# Erls_MCP73871_Solar_Charger_v1.net
KiCad netlist of a schematic drawn in EAGLE
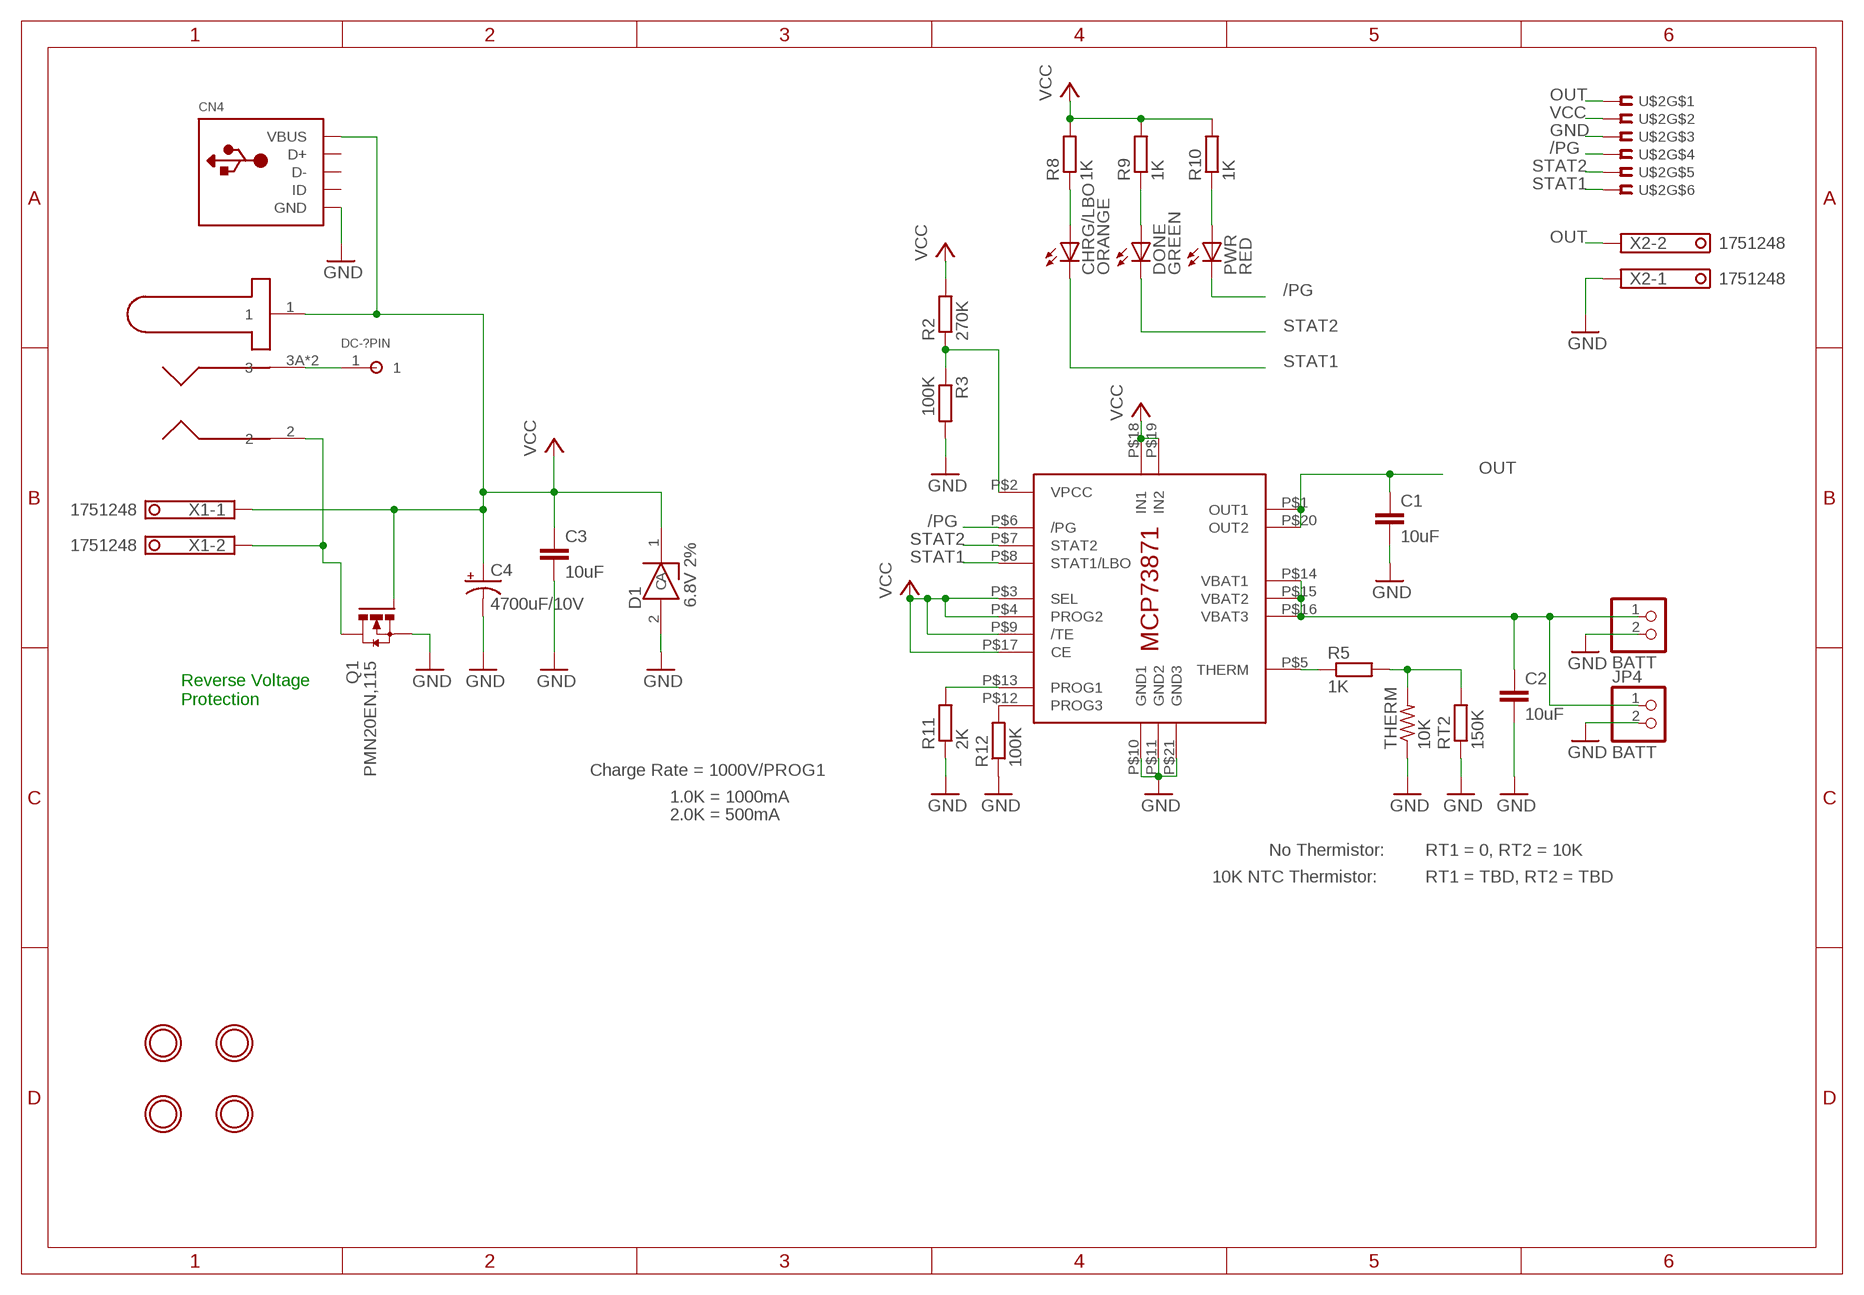
[diagram p0: schematic, sheet 1]

(export (version "E")
  (design (tool "Eeschema 10.0.6"))
  (components
    (comp (ref "BATT")
      (value "JST_2PIN-SMT-RA")
      (footprint "eagle-import:JST-PH-2-SMT-RA")
      (libsource (lib "eagle-import") (part "JST_2PIN-SMT-RA"))
    )
    (comp (ref "C1")
      (value "10uF")
      (footprint "eagle-import:C0603K")
      (libsource (lib "eagle-import") (part "C-EUC0603K"))
    )
    (comp (ref "C2")
      (value "10uF")
      (footprint "eagle-import:C0603K")
      (libsource (lib "eagle-import") (part "C-EUC0603K"))
    )
    (comp (ref "C3")
      (value "10uF")
      (footprint "eagle-import:C0603K")
      (libsource (lib "eagle-import") (part "C-EUC0603K"))
    )
    (comp (ref "C4")
      (value "4700uF/10V")
      (footprint "eagle-import:E5-13")
      (libsource (lib "eagle-import") (part "CPOL-USE5-13"))
    )
    (comp (ref "CHRG/LBO")
      (value "ORANGE")
      (footprint "eagle-import:CHIPLED_0603")
      (libsource (lib "eagle-import") (part "LED-0603"))
    )
    (comp (ref "CN4")
      (value "USB-MINIB-ONSHORE-M26FTR")
      (footprint "eagle-import:USB-MINIB-ONSHORE-M26FTR")
      (libsource (lib "eagle-import") (part "USB-MINIB-ONSHORE-M26FTR"))
    )
    (comp (ref "D1")
      (value "6.8V 2%")
      (footprint "eagle-import:SOD323")
      (libsource (lib "eagle-import") (part "ZENER-MM3Z6V8ST1G"))
    )
    (comp (ref "DC-?PIN")
      (value "PAD-1-TH")
      (footprint "eagle-import:PAD-1-TH")
      (libsource (lib "eagle-import") (part "PAD-1-TH"))
    )
    (comp (ref "DONE")
      (value "GREEN")
      (footprint "eagle-import:CHIPLED_0603")
      (libsource (lib "eagle-import") (part "LED-0603"))
    )
    (comp (ref "JP4")
      (value "BATT")
      (footprint "eagle-import:1X02_ROUND")
      (libsource (lib "eagle-import") (part "HEADER-1X2ROUND"))
    )
    (comp (ref "PWR")
      (value "RED")
      (footprint "eagle-import:CHIPLED_0603")
      (libsource (lib "eagle-import") (part "LED-0603"))
    )
    (comp (ref "Q1")
      (value "PMN20EN,115")
      (footprint "eagle-import:SOT457R_PHILIPS")
      (libsource (lib "eagle-import") (part "PMN20EN,115"))
    )
    (comp (ref "R2")
      (value "270K")
      (footprint "eagle-import:R0603")
      (libsource (lib "eagle-import") (part "R-EU_R0603"))
    )
    (comp (ref "R3")
      (value "100K")
      (footprint "eagle-import:R0603")
      (libsource (lib "eagle-import") (part "R-EU_R0603"))
    )
    (comp (ref "R5")
      (value "1K")
      (footprint "eagle-import:R0603")
      (libsource (lib "eagle-import") (part "R-EU_R0603"))
    )
    (comp (ref "R8")
      (value "1K")
      (footprint "eagle-import:R0603")
      (libsource (lib "eagle-import") (part "R-EU_R0603"))
    )
    (comp (ref "R9")
      (value "1K")
      (footprint "eagle-import:R0603")
      (libsource (lib "eagle-import") (part "R-EU_R0603"))
    )
    (comp (ref "R10")
      (value "1K")
      (footprint "eagle-import:R0603")
      (libsource (lib "eagle-import") (part "R-EU_R0603"))
    )
    (comp (ref "R11")
      (value "2K")
      (footprint "eagle-import:R0603")
      (libsource (lib "eagle-import") (part "R-EU_R0603"))
    )
    (comp (ref "R12")
      (value "100K")
      (footprint "eagle-import:R0603")
      (libsource (lib "eagle-import") (part "R-EU_R0603"))
    )
    (comp (ref "RT2")
      (value "150K")
      (footprint "eagle-import:R0603")
      (libsource (lib "eagle-import") (part "R-EU_R0603"))
    )
    (comp (ref "THERM")
      (value "10K")
      (footprint "eagle-import:0805-THM")
      (libsource (lib "eagle-import") (part "R-US_FLIPFLOP"))
    )
    (comp (ref "U$1")
      (value "DJACK-NOSW-CUI-PJ028-SMT")
      (footprint "eagle-import:DCJACK-CUI-PJ028-SMT")
      (libsource (lib "eagle-import") (part "DJACK-NOSW-CUI-PJ028-SMT"))
    )
    (comp (ref "U$2")
      (value "FE06-1W-MOLEX-KK-22-15-2026")
      (footprint "eagle-import:MOLEX-KK-22-15-2026-6")
      (libsource (lib "eagle-import") (part "FE06-1W-MOLEX-KK-22-15-2026"))
    )
    (comp (ref "U$4")
      (value "MOUNTINGHOLE2.5")
      (footprint "eagle-import:MOUNTINGHOLE_2.5_PLATED")
      (libsource (lib "eagle-import") (part "MOUNTINGHOLE2.5"))
    )
    (comp (ref "U$5")
      (value "MOUNTINGHOLE2.5")
      (footprint "eagle-import:MOUNTINGHOLE_2.5_PLATED")
      (libsource (lib "eagle-import") (part "MOUNTINGHOLE2.5"))
    )
    (comp (ref "U$6")
      (value "MOUNTINGHOLE2.5")
      (footprint "eagle-import:MOUNTINGHOLE_2.5_PLATED")
      (libsource (lib "eagle-import") (part "MOUNTINGHOLE2.5"))
    )
    (comp (ref "U$7")
      (value "MOUNTINGHOLE2.5")
      (footprint "eagle-import:MOUNTINGHOLE_2.5_PLATED")
      (libsource (lib "eagle-import") (part "MOUNTINGHOLE2.5"))
    )
    (comp (ref "U1")
      (value "MCP73871")
      (footprint "eagle-import:QFN20_4MM")
      (libsource (lib "eagle-import") (part "MCP73871"))
    )
    (comp (ref "X1")
      (value "1751248")
      (footprint "eagle-import:1751248")
      (libsource (lib "eagle-import") (part "1751248"))
    )
    (comp (ref "X2")
      (value "1751248")
      (footprint "eagle-import:1751248")
      (libsource (lib "eagle-import") (part "1751248"))
    )
  )
  (nets
    (net (code "1") (name "/OUT") (class "Default")
      (node (ref "C1") (pin "1") (pinfunction "1_1") (pintype "passive"))
      (node (ref "U$2") (pin "1") (pinfunction "S_1") (pintype "passive"))
      (node (ref "U1") (pin "P$1") (pinfunction "OUT1_P$1") (pintype "output"))
      (node (ref "U1") (pin "P$20") (pinfunction "OUT2_P$20") (pintype "output"))
      (node (ref "X2") (pin "2") (pinfunction "K_2") (pintype "passive"))
    )
    (net (code "2") (name "/STAT1") (class "Default")
      (node (ref "CHRG/LBO") (pin "C") (pinfunction "C_C") (pintype "passive"))
      (node (ref "U$2") (pin "6") (pinfunction "S_6") (pintype "passive"))
      (node (ref "U1") (pin "P$8") (pinfunction "STAT1/LBO_P$8") (pintype "output"))
    )
    (net (code "3") (name "/STAT2") (class "Default")
      (node (ref "DONE") (pin "C") (pinfunction "C_C") (pintype "passive"))
      (node (ref "U$2") (pin "5") (pinfunction "S_5") (pintype "passive"))
      (node (ref "U1") (pin "P$7") (pinfunction "STAT2_P$7") (pintype "output"))
    )
    (net (code "4") (name "/{slash}PG") (class "Default")
      (node (ref "PWR") (pin "C") (pinfunction "C_C") (pintype "passive"))
      (node (ref "U$2") (pin "4") (pinfunction "S_4") (pintype "passive"))
      (node (ref "U1") (pin "P$6") (pinfunction "/PG_P$6") (pintype "output"))
    )
    (net (code "5") (name "GND") (class "Default")
      (node (ref "BATT") (pin "2") (pinfunction "1_2") (pintype "passive"))
      (node (ref "C1") (pin "2") (pinfunction "2_2") (pintype "passive"))
      (node (ref "C2") (pin "2") (pinfunction "2_2") (pintype "passive"))
      (node (ref "C3") (pin "2") (pinfunction "2_2") (pintype "passive"))
      (node (ref "C4") (pin "-") (pinfunction "-_-") (pintype "passive"))
      (node (ref "CN4") (pin "5") (pinfunction "GND_5") (pintype "power_in"))
      (node (ref "D1") (pin "2") (pinfunction "A_2") (pintype "passive"))
      (node (ref "JP4") (pin "2") (pinfunction "2_2") (pintype "passive"))
      (node (ref "Q1") (pin "4") (pinfunction "S_4") (pintype "passive"))
      (node (ref "R11") (pin "1") (pinfunction "1_1") (pintype "passive"))
      (node (ref "R12") (pin "1") (pinfunction "1_1") (pintype "passive"))
      (node (ref "R3") (pin "2") (pinfunction "2_2") (pintype "passive"))
      (node (ref "RT2") (pin "1") (pinfunction "1_1") (pintype "passive"))
      (node (ref "THERM") (pin "1") (pinfunction "1_1") (pintype "passive"))
      (node (ref "U$2") (pin "3") (pinfunction "S_3") (pintype "passive"))
      (node (ref "U1") (pin "P$10") (pinfunction "GND1_P$10") (pintype "power_in"))
      (node (ref "U1") (pin "P$11") (pinfunction "GND2_P$11") (pintype "power_in"))
      (node (ref "U1") (pin "P$21") (pinfunction "GND3_P$21") (pintype "power_in"))
      (node (ref "X2") (pin "1") (pinfunction "K_1") (pintype "passive"))
    )
    (net (code "6") (name "Net-(BATT-2)") (class "Default")
      (node (ref "BATT") (pin "1") (pinfunction "2_1") (pintype "passive"))
      (node (ref "C2") (pin "1") (pinfunction "1_1") (pintype "passive"))
      (node (ref "JP4") (pin "1") (pinfunction "1_1") (pintype "passive"))
      (node (ref "U1") (pin "P$14") (pinfunction "VBAT1_P$14") (pintype "output"))
      (node (ref "U1") (pin "P$15") (pinfunction "VBAT2_P$15") (pintype "output"))
      (node (ref "U1") (pin "P$16") (pinfunction "VBAT3_P$16") (pintype "output"))
    )
    (net (code "7") (name "Net-(CHRG/LBO-PadA)") (class "Default")
      (node (ref "CHRG/LBO") (pin "A") (pinfunction "A_A") (pintype "passive"))
      (node (ref "R8") (pin "1") (pinfunction "1_1") (pintype "passive"))
    )
    (net (code "8") (name "Net-(DC-?PIN-Pad1)") (class "Default")
      (node (ref "DC-?PIN") (pin "1") (pinfunction "1_1") (pintype "bidirectional"))
      (node (ref "U$1") (pin "3A") (pinfunction "3_3A") (pintype "passive"))
      (node (ref "U$1") (pin "3B") (pinfunction "3_3B") (pintype "passive"))
    )
    (net (code "9") (name "Net-(DONE-PadA)") (class "Default")
      (node (ref "DONE") (pin "A") (pinfunction "A_A") (pintype "passive"))
      (node (ref "R9") (pin "1") (pinfunction "1_1") (pintype "passive"))
    )
    (net (code "10") (name "Net-(PWR-PadA)") (class "Default")
      (node (ref "PWR") (pin "A") (pinfunction "A_A") (pintype "passive"))
      (node (ref "R10") (pin "1") (pinfunction "1_1") (pintype "passive"))
    )
    (net (code "11") (name "Net-(R5-Pad2)") (class "Default")
      (node (ref "R5") (pin "2") (pinfunction "2_2") (pintype "passive"))
      (node (ref "RT2") (pin "2") (pinfunction "2_2") (pintype "passive"))
      (node (ref "THERM") (pin "2") (pinfunction "2_2") (pintype "passive"))
    )
    (net (code "12") (name "Net-(U1-PROG1)") (class "Default")
      (node (ref "R11") (pin "2") (pinfunction "2_2") (pintype "passive"))
      (node (ref "U1") (pin "P$13") (pinfunction "PROG1_P$13") (pintype "input"))
    )
    (net (code "13") (name "Net-(U1-PROG3)") (class "Default")
      (node (ref "R12") (pin "2") (pinfunction "2_2") (pintype "passive"))
      (node (ref "U1") (pin "P$12") (pinfunction "PROG3_P$12") (pintype "input"))
    )
    (net (code "14") (name "Net-(U1-THERM)") (class "Default")
      (node (ref "R5") (pin "1") (pinfunction "1_1") (pintype "passive"))
      (node (ref "U1") (pin "P$5") (pinfunction "THERM_P$5") (pintype "input"))
    )
    (net (code "15") (name "Net-(U1-VPCC)") (class "Default")
      (node (ref "R2") (pin "1") (pinfunction "1_1") (pintype "passive"))
      (node (ref "R3") (pin "1") (pinfunction "1_1") (pintype "passive"))
      (node (ref "U1") (pin "P$2") (pinfunction "VPCC_P$2") (pintype "input"))
    )
    (net (code "16") (name "Net-(X1B-K)") (class "Default")
      (node (ref "Q1") (pin "1") (pinfunction "D_1") (pintype "passive"))
      (node (ref "Q1") (pin "2") (pinfunction "D_2") (pintype "passive"))
      (node (ref "Q1") (pin "5") (pinfunction "D_5") (pintype "passive"))
      (node (ref "Q1") (pin "6") (pinfunction "D_6") (pintype "passive"))
      (node (ref "U$1") (pin "2") (pinfunction "2_2") (pintype "passive"))
      (node (ref "X1") (pin "2") (pinfunction "K_2") (pintype "passive"))
    )
    (net (code "17") (name "VCC") (class "Default")
      (node (ref "C3") (pin "1") (pinfunction "1_1") (pintype "passive"))
      (node (ref "C4") (pin "+") (pinfunction "+_+") (pintype "passive"))
      (node (ref "CN4") (pin "1") (pinfunction "VBUS_1") (pintype "power_in"))
      (node (ref "D1") (pin "1") (pinfunction "C_1") (pintype "passive"))
      (node (ref "Q1") (pin "3") (pinfunction "G_3") (pintype "passive"))
      (node (ref "R10") (pin "2") (pinfunction "2_2") (pintype "passive"))
      (node (ref "R2") (pin "2") (pinfunction "2_2") (pintype "passive"))
      (node (ref "R8") (pin "2") (pinfunction "2_2") (pintype "passive"))
      (node (ref "R9") (pin "2") (pinfunction "2_2") (pintype "passive"))
      (node (ref "U$1") (pin "1") (pinfunction "1_1") (pintype "passive"))
      (node (ref "U$2") (pin "2") (pinfunction "S_2") (pintype "passive"))
      (node (ref "U1") (pin "P$17") (pinfunction "CE_P$17") (pintype "input"))
      (node (ref "U1") (pin "P$18") (pinfunction "IN1_P$18") (pintype "input"))
      (node (ref "U1") (pin "P$19") (pinfunction "IN2_P$19") (pintype "input"))
      (node (ref "U1") (pin "P$3") (pinfunction "SEL_P$3") (pintype "input"))
      (node (ref "U1") (pin "P$4") (pinfunction "PROG2_P$4") (pintype "input"))
      (node (ref "U1") (pin "P$9") (pinfunction "/TE_P$9") (pintype "input"))
      (node (ref "X1") (pin "1") (pinfunction "K_1") (pintype "passive"))
    )
    (net (code "18") (name "unconnected-(CN4-D+-Pad3)") (class "Default")
      (node (ref "CN4") (pin "3") (pinfunction "D+_3") (pintype "bidirectional"))
    )
    (net (code "19") (name "unconnected-(CN4-D--Pad2)") (class "Default")
      (node (ref "CN4") (pin "2") (pinfunction "D-_2") (pintype "bidirectional"))
    )
    (net (code "20") (name "unconnected-(CN4-ID-Pad4)") (class "Default")
      (node (ref "CN4") (pin "4") (pinfunction "ID_4") (pintype "bidirectional"))
    )
  )
)
